# QCopterFC_PWM_Sch.net
KiCad netlist of a schematic drawn in Altium Designer
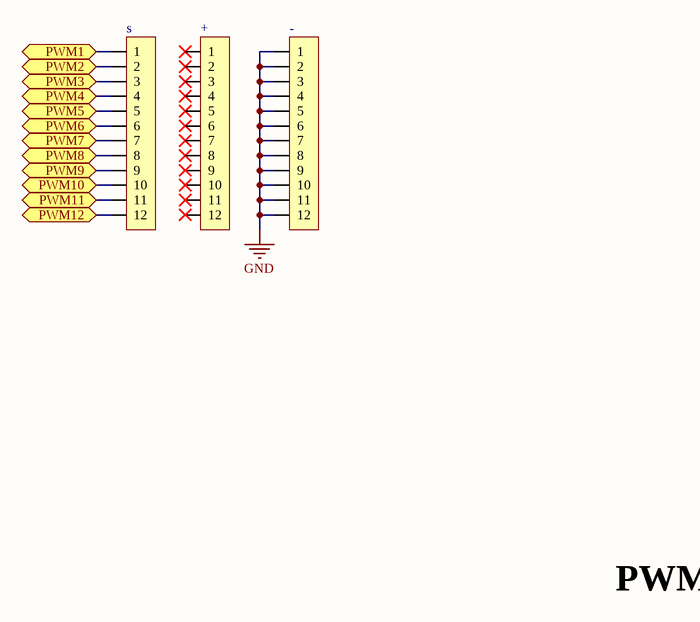
[diagram p0: QCopterFC_PWM_Sch.SchDoc]

(export (version "E")
  (design (tool "Eeschema 10.0.6"))
  (components
    (comp (ref "+")
      (value "HDR1X12_180_2.54")
      (footprint "PCB_Connector:HDR1X12_180_2.54")
      (description "Header")
      (libsource (lib "SCH_Connector") (part "HDR1X12_180_2.54"))
    )
    (comp (ref "-")
      (value "HDR1X12_180_2.54")
      (footprint "PCB_Connector:HDR1X12_180_2.54")
      (description "Header")
      (libsource (lib "SCH_Connector") (part "HDR1X12_180_2.54"))
    )
    (comp (ref "s")
      (value "HDR1X12_180_2.54")
      (footprint "PCB_Connector:HDR1X12_180_2.54")
      (description "Header")
      (libsource (lib "SCH_Connector") (part "HDR1X12_180_2.54"))
    )
  )
  (nets
    (net (code "1") (name "/PWM1") (class "Default")
      (node (ref "s") (pin "1") (pinfunction "1_1") (pintype "passive"))
    )
    (net (code "2") (name "/PWM2") (class "Default")
      (node (ref "s") (pin "2") (pinfunction "2_2") (pintype "passive"))
    )
    (net (code "3") (name "/PWM3") (class "Default")
      (node (ref "s") (pin "3") (pinfunction "3_3") (pintype "passive"))
    )
    (net (code "4") (name "/PWM4") (class "Default")
      (node (ref "s") (pin "4") (pinfunction "4_4") (pintype "passive"))
    )
    (net (code "5") (name "/PWM5") (class "Default")
      (node (ref "s") (pin "5") (pinfunction "5_5") (pintype "passive"))
    )
    (net (code "6") (name "/PWM6") (class "Default")
      (node (ref "s") (pin "6") (pinfunction "6_6") (pintype "passive"))
    )
    (net (code "7") (name "/PWM7") (class "Default")
      (node (ref "s") (pin "7") (pinfunction "7_7") (pintype "passive"))
    )
    (net (code "8") (name "/PWM8") (class "Default")
      (node (ref "s") (pin "8") (pinfunction "8_8") (pintype "passive"))
    )
    (net (code "9") (name "/PWM9") (class "Default")
      (node (ref "s") (pin "9") (pinfunction "9_9") (pintype "passive"))
    )
    (net (code "10") (name "/PWM10") (class "Default")
      (node (ref "s") (pin "10") (pinfunction "10_10") (pintype "passive"))
    )
    (net (code "11") (name "/PWM11") (class "Default")
      (node (ref "s") (pin "11") (pinfunction "11_11") (pintype "passive"))
    )
    (net (code "12") (name "/PWM12") (class "Default")
      (node (ref "s") (pin "12") (pinfunction "12_12") (pintype "passive"))
    )
    (net (code "13") (name "GND") (class "Default")
      (node (ref "-") (pin "1") (pinfunction "1_1") (pintype "passive"))
      (node (ref "-") (pin "10") (pinfunction "10_10") (pintype "passive"))
      (node (ref "-") (pin "11") (pinfunction "11_11") (pintype "passive"))
      (node (ref "-") (pin "12") (pinfunction "12_12") (pintype "passive"))
      (node (ref "-") (pin "2") (pinfunction "2_2") (pintype "passive"))
      (node (ref "-") (pin "3") (pinfunction "3_3") (pintype "passive"))
      (node (ref "-") (pin "4") (pinfunction "4_4") (pintype "passive"))
      (node (ref "-") (pin "5") (pinfunction "5_5") (pintype "passive"))
      (node (ref "-") (pin "6") (pinfunction "6_6") (pintype "passive"))
      (node (ref "-") (pin "7") (pinfunction "7_7") (pintype "passive"))
      (node (ref "-") (pin "8") (pinfunction "8_8") (pintype "passive"))
      (node (ref "-") (pin "9") (pinfunction "9_9") (pintype "passive"))
    )
    (net (code "14") (name "unconnected-(+-Pad1)") (class "Default")
      (node (ref "+") (pin "1") (pinfunction "1_1") (pintype "passive+no_connect"))
    )
    (net (code "15") (name "unconnected-(+-Pad2)") (class "Default")
      (node (ref "+") (pin "2") (pinfunction "2_2") (pintype "passive+no_connect"))
    )
    (net (code "16") (name "unconnected-(+-Pad3)") (class "Default")
      (node (ref "+") (pin "3") (pinfunction "3_3") (pintype "passive+no_connect"))
    )
    (net (code "17") (name "unconnected-(+-Pad4)") (class "Default")
      (node (ref "+") (pin "4") (pinfunction "4_4") (pintype "passive+no_connect"))
    )
    (net (code "18") (name "unconnected-(+-Pad5)") (class "Default")
      (node (ref "+") (pin "5") (pinfunction "5_5") (pintype "passive+no_connect"))
    )
    (net (code "19") (name "unconnected-(+-Pad6)") (class "Default")
      (node (ref "+") (pin "6") (pinfunction "6_6") (pintype "passive+no_connect"))
    )
    (net (code "20") (name "unconnected-(+-Pad7)") (class "Default")
      (node (ref "+") (pin "7") (pinfunction "7_7") (pintype "passive+no_connect"))
    )
    (net (code "21") (name "unconnected-(+-Pad8)") (class "Default")
      (node (ref "+") (pin "8") (pinfunction "8_8") (pintype "passive+no_connect"))
    )
    (net (code "22") (name "unconnected-(+-Pad9)") (class "Default")
      (node (ref "+") (pin "9") (pinfunction "9_9") (pintype "passive+no_connect"))
    )
    (net (code "23") (name "unconnected-(+-Pad10)") (class "Default")
      (node (ref "+") (pin "10") (pinfunction "10_10") (pintype "passive+no_connect"))
    )
    (net (code "24") (name "unconnected-(+-Pad11)") (class "Default")
      (node (ref "+") (pin "11") (pinfunction "11_11") (pintype "passive+no_connect"))
    )
    (net (code "25") (name "unconnected-(+-Pad12)") (class "Default")
      (node (ref "+") (pin "12") (pinfunction "12_12") (pintype "passive+no_connect"))
    )
  )
)
